# claude-micro-easyeda.net
KiCad netlist of a schematic drawn in EasyEDA
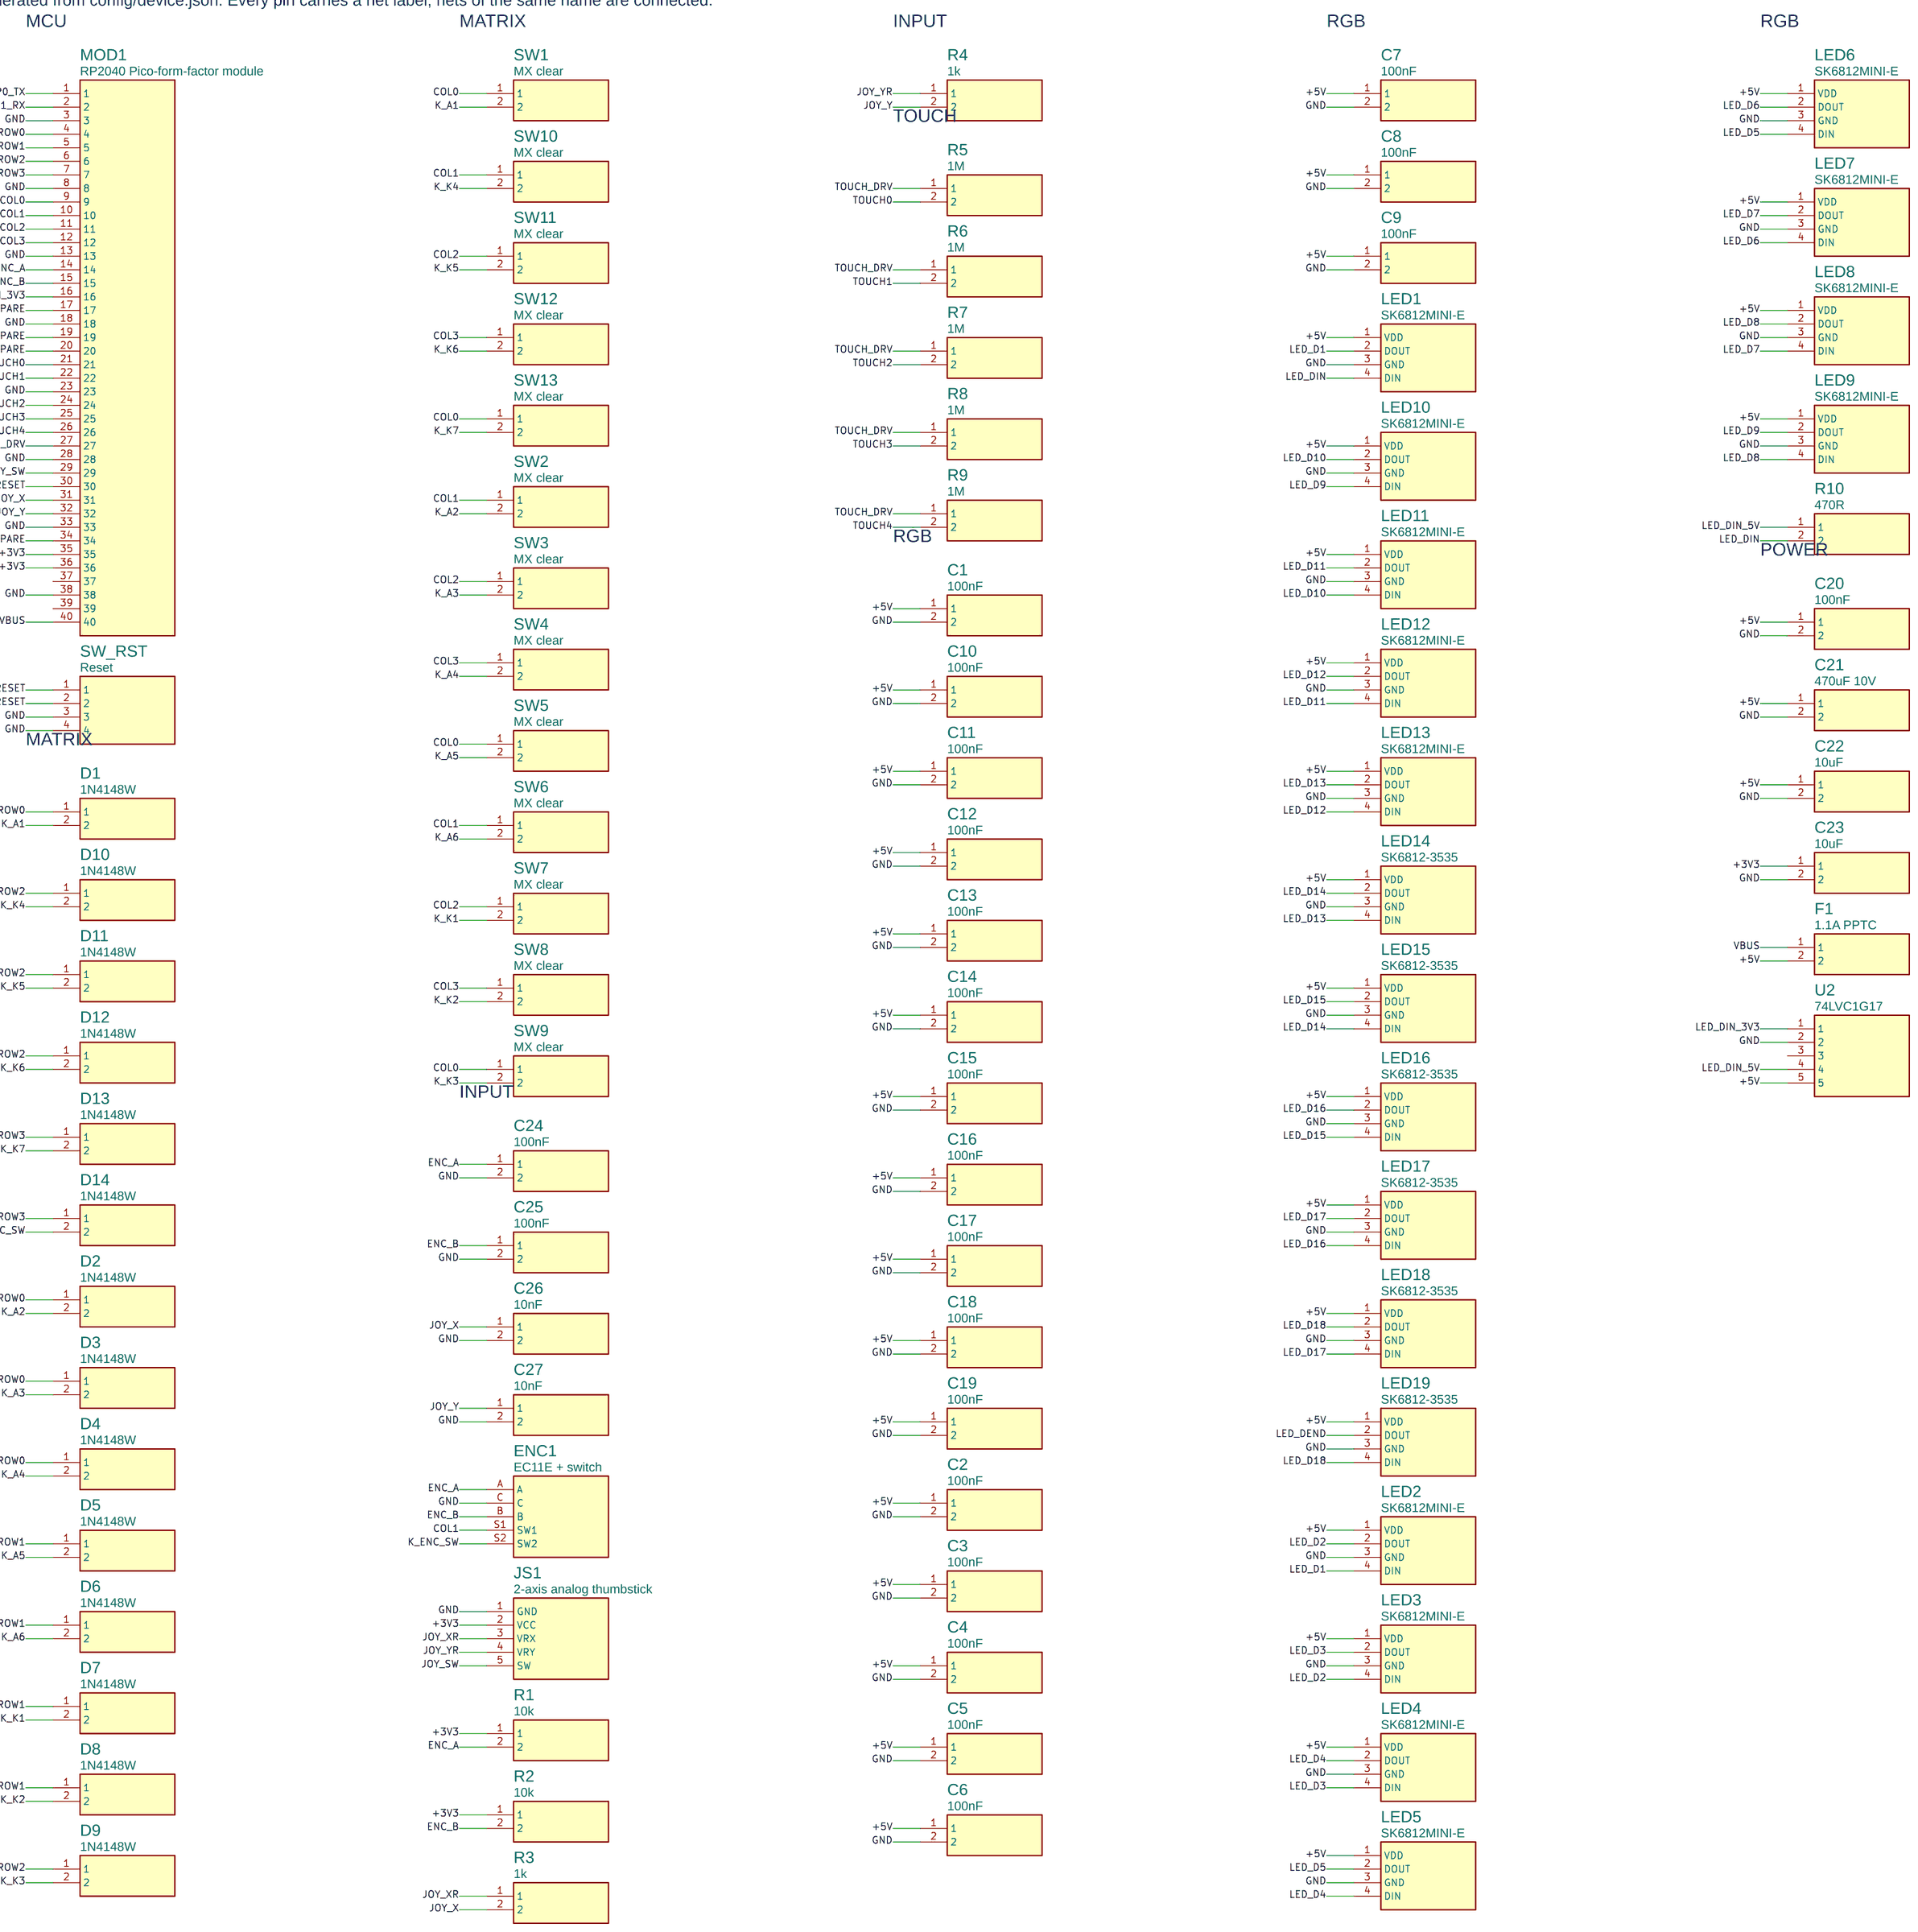
[diagram p0: schematic sheet]

(export (version "E")
  (design (tool "Eeschema 10.0.6"))
  (components
    (comp (ref "C1") (value "100nF") (libsource (lib "") (part "100nF")))
    (comp (ref "C2") (value "100nF") (libsource (lib "") (part "100nF")))
    (comp (ref "C3") (value "100nF") (libsource (lib "") (part "100nF")))
    (comp (ref "C4") (value "100nF") (libsource (lib "") (part "100nF")))
    (comp (ref "C5") (value "100nF") (libsource (lib "") (part "100nF")))
    (comp (ref "C6") (value "100nF") (libsource (lib "") (part "100nF")))
    (comp (ref "C7") (value "100nF") (libsource (lib "") (part "100nF")))
    (comp (ref "C8") (value "100nF") (libsource (lib "") (part "100nF")))
    (comp (ref "C9") (value "100nF") (libsource (lib "") (part "100nF")))
    (comp (ref "C10") (value "100nF") (libsource (lib "") (part "100nF")))
    (comp (ref "C11") (value "100nF") (libsource (lib "") (part "100nF")))
    (comp (ref "C12") (value "100nF") (libsource (lib "") (part "100nF")))
    (comp (ref "C13") (value "100nF") (libsource (lib "") (part "100nF")))
    (comp (ref "C14") (value "100nF") (libsource (lib "") (part "100nF")))
    (comp (ref "C15") (value "100nF") (libsource (lib "") (part "100nF")))
    (comp (ref "C16") (value "100nF") (libsource (lib "") (part "100nF")))
    (comp (ref "C17") (value "100nF") (libsource (lib "") (part "100nF")))
    (comp (ref "C18") (value "100nF") (libsource (lib "") (part "100nF")))
    (comp (ref "C19") (value "100nF") (libsource (lib "") (part "100nF")))
    (comp (ref "C20") (value "100nF") (libsource (lib "") (part "100nF")))
    (comp (ref "C21")
      (value "470uF 10V")
      (fields (field (name "BOM_Manufacturer Part") "Low-ESR bulk"))
      (libsource (lib "") (part "470uF 10V"))
    )
    (comp (ref "C22") (value "10uF") (libsource (lib "") (part "10uF")))
    (comp (ref "C23") (value "10uF") (libsource (lib "") (part "10uF")))
    (comp (ref "C24") (value "100nF") (libsource (lib "") (part "100nF_1")))
    (comp (ref "C25") (value "100nF") (libsource (lib "") (part "100nF_1")))
    (comp (ref "C26") (value "10nF") (libsource (lib "") (part "10nF")))
    (comp (ref "C27") (value "10nF") (libsource (lib "") (part "10nF")))
    (comp (ref "D1")
      (value "1N4148W")
      (fields (field (name "BOM_Manufacturer Part") "1N4148W SOD-123"))
      (libsource (lib "") (part "1N4148W"))
    )
    (comp (ref "D2")
      (value "1N4148W")
      (fields (field (name "BOM_Manufacturer Part") "1N4148W SOD-123"))
      (libsource (lib "") (part "1N4148W"))
    )
    (comp (ref "D3")
      (value "1N4148W")
      (fields (field (name "BOM_Manufacturer Part") "1N4148W SOD-123"))
      (libsource (lib "") (part "1N4148W"))
    )
    (comp (ref "D4")
      (value "1N4148W")
      (fields (field (name "BOM_Manufacturer Part") "1N4148W SOD-123"))
      (libsource (lib "") (part "1N4148W"))
    )
    (comp (ref "D5")
      (value "1N4148W")
      (fields (field (name "BOM_Manufacturer Part") "1N4148W SOD-123"))
      (libsource (lib "") (part "1N4148W"))
    )
    (comp (ref "D6")
      (value "1N4148W")
      (fields (field (name "BOM_Manufacturer Part") "1N4148W SOD-123"))
      (libsource (lib "") (part "1N4148W"))
    )
    (comp (ref "D7")
      (value "1N4148W")
      (fields (field (name "BOM_Manufacturer Part") "1N4148W SOD-123"))
      (libsource (lib "") (part "1N4148W"))
    )
    (comp (ref "D8")
      (value "1N4148W")
      (fields (field (name "BOM_Manufacturer Part") "1N4148W SOD-123"))
      (libsource (lib "") (part "1N4148W"))
    )
    (comp (ref "D9")
      (value "1N4148W")
      (fields (field (name "BOM_Manufacturer Part") "1N4148W SOD-123"))
      (libsource (lib "") (part "1N4148W"))
    )
    (comp (ref "D10")
      (value "1N4148W")
      (fields (field (name "BOM_Manufacturer Part") "1N4148W SOD-123"))
      (libsource (lib "") (part "1N4148W"))
    )
    (comp (ref "D11")
      (value "1N4148W")
      (fields (field (name "BOM_Manufacturer Part") "1N4148W SOD-123"))
      (libsource (lib "") (part "1N4148W"))
    )
    (comp (ref "D12")
      (value "1N4148W")
      (fields (field (name "BOM_Manufacturer Part") "1N4148W SOD-123"))
      (libsource (lib "") (part "1N4148W"))
    )
    (comp (ref "D13")
      (value "1N4148W")
      (fields (field (name "BOM_Manufacturer Part") "1N4148W SOD-123"))
      (libsource (lib "") (part "1N4148W"))
    )
    (comp (ref "D14")
      (value "1N4148W")
      (fields (field (name "BOM_Manufacturer Part") "1N4148W SOD-123"))
      (libsource (lib "") (part "1N4148W"))
    )
    (comp (ref "ENC1")
      (value "EC11E + switch")
      (fields (field (name "BOM_Manufacturer Part") "EC11E15244Ax (9 mm shaft)"))
      (libsource (lib "") (part "EC11E + switch"))
    )
    (comp (ref "F1")
      (value "1.1A PPTC")
      (fields (field (name "BOM_Manufacturer Part") "MF-MSMF110"))
      (libsource (lib "") (part "1.1A PPTC"))
    )
    (comp (ref "JS1")
      (value "2-axis analog thumbstick")
      (fields (field (name "BOM_Manufacturer Part") "20 mm planar thumbstick, 10k pots"))
      (libsource (lib "") (part "2-axis analog thumbstick"))
    )
    (comp (ref "LED1") (value "SK6812MINI-E") (libsource (lib "") (part "SK6812MINI-E")))
    (comp (ref "LED2") (value "SK6812MINI-E") (libsource (lib "") (part "SK6812MINI-E")))
    (comp (ref "LED3") (value "SK6812MINI-E") (libsource (lib "") (part "SK6812MINI-E")))
    (comp (ref "LED4") (value "SK6812MINI-E") (libsource (lib "") (part "SK6812MINI-E")))
    (comp (ref "LED5") (value "SK6812MINI-E") (libsource (lib "") (part "SK6812MINI-E")))
    (comp (ref "LED6") (value "SK6812MINI-E") (libsource (lib "") (part "SK6812MINI-E")))
    (comp (ref "LED7") (value "SK6812MINI-E") (libsource (lib "") (part "SK6812MINI-E")))
    (comp (ref "LED8") (value "SK6812MINI-E") (libsource (lib "") (part "SK6812MINI-E")))
    (comp (ref "LED9") (value "SK6812MINI-E") (libsource (lib "") (part "SK6812MINI-E")))
    (comp (ref "LED10") (value "SK6812MINI-E") (libsource (lib "") (part "SK6812MINI-E")))
    (comp (ref "LED11") (value "SK6812MINI-E") (libsource (lib "") (part "SK6812MINI-E")))
    (comp (ref "LED12") (value "SK6812MINI-E") (libsource (lib "") (part "SK6812MINI-E")))
    (comp (ref "LED13") (value "SK6812MINI-E") (libsource (lib "") (part "SK6812MINI-E")))
    (comp (ref "LED14") (value "SK6812-3535") (libsource (lib "") (part "SK6812-3535")))
    (comp (ref "LED15") (value "SK6812-3535") (libsource (lib "") (part "SK6812-3535")))
    (comp (ref "LED16") (value "SK6812-3535") (libsource (lib "") (part "SK6812-3535")))
    (comp (ref "LED17") (value "SK6812-3535") (libsource (lib "") (part "SK6812-3535")))
    (comp (ref "LED18") (value "SK6812-3535") (libsource (lib "") (part "SK6812-3535")))
    (comp (ref "LED19") (value "SK6812-3535") (libsource (lib "") (part "SK6812-3535")))
    (comp (ref "MOD1")
      (value "RP2040 Pico-form-factor module")
      (fields (field (name "BOM_Manufacturer Part") "YD-RP2040 / RP2040-Plus / Raspberry Pi Pico"))
      (libsource (lib "") (part "RP2040 Pico-form-factor module"))
    )
    (comp (ref "R1") (value "10k") (libsource (lib "") (part "10k")))
    (comp (ref "R2") (value "10k") (libsource (lib "") (part "10k")))
    (comp (ref "R3") (value "1k") (libsource (lib "") (part "1k")))
    (comp (ref "R4") (value "1k") (libsource (lib "") (part "1k")))
    (comp (ref "R5") (value "1M") (libsource (lib "") (part "1M")))
    (comp (ref "R6") (value "1M") (libsource (lib "") (part "1M")))
    (comp (ref "R7") (value "1M") (libsource (lib "") (part "1M")))
    (comp (ref "R8") (value "1M") (libsource (lib "") (part "1M")))
    (comp (ref "R9") (value "1M") (libsource (lib "") (part "1M")))
    (comp (ref "R10") (value "470R") (libsource (lib "") (part "470R")))
    (comp (ref "SW1")
      (value "MX clear")
      (fields (field (name "BOM_Manufacturer Part") "MX-compatible, clear housing, 5-pin"))
      (libsource (lib "") (part "MX clear"))
    )
    (comp (ref "SW2")
      (value "MX clear")
      (fields (field (name "BOM_Manufacturer Part") "MX-compatible, clear housing, 5-pin"))
      (libsource (lib "") (part "MX clear"))
    )
    (comp (ref "SW3")
      (value "MX clear")
      (fields (field (name "BOM_Manufacturer Part") "MX-compatible, clear housing, 5-pin"))
      (libsource (lib "") (part "MX clear"))
    )
    (comp (ref "SW4")
      (value "MX clear")
      (fields (field (name "BOM_Manufacturer Part") "MX-compatible, clear housing, 5-pin"))
      (libsource (lib "") (part "MX clear"))
    )
    (comp (ref "SW5")
      (value "MX clear")
      (fields (field (name "BOM_Manufacturer Part") "MX-compatible, clear housing, 5-pin"))
      (libsource (lib "") (part "MX clear"))
    )
    (comp (ref "SW6")
      (value "MX clear")
      (fields (field (name "BOM_Manufacturer Part") "MX-compatible, clear housing, 5-pin"))
      (libsource (lib "") (part "MX clear"))
    )
    (comp (ref "SW7")
      (value "MX clear")
      (fields (field (name "BOM_Manufacturer Part") "MX-compatible, clear housing, 5-pin"))
      (libsource (lib "") (part "MX clear"))
    )
    (comp (ref "SW8")
      (value "MX clear")
      (fields (field (name "BOM_Manufacturer Part") "MX-compatible, clear housing, 5-pin"))
      (libsource (lib "") (part "MX clear"))
    )
    (comp (ref "SW9")
      (value "MX clear")
      (fields (field (name "BOM_Manufacturer Part") "MX-compatible, clear housing, 5-pin"))
      (libsource (lib "") (part "MX clear"))
    )
    (comp (ref "SW10")
      (value "MX clear")
      (fields (field (name "BOM_Manufacturer Part") "MX-compatible, clear housing, 5-pin"))
      (libsource (lib "") (part "MX clear"))
    )
    (comp (ref "SW11")
      (value "MX clear")
      (fields (field (name "BOM_Manufacturer Part") "MX-compatible, clear housing, 5-pin"))
      (libsource (lib "") (part "MX clear"))
    )
    (comp (ref "SW12")
      (value "MX clear")
      (fields (field (name "BOM_Manufacturer Part") "MX-compatible, clear housing, 5-pin"))
      (libsource (lib "") (part "MX clear"))
    )
    (comp (ref "SW13")
      (value "MX clear")
      (fields (field (name "BOM_Manufacturer Part") "MX-compatible, clear housing, 5-pin"))
      (libsource (lib "") (part "MX clear"))
    )
    (comp (ref "SW_RST") (value "Reset") (libsource (lib "") (part "Reset")))
    (comp (ref "U2")
      (value "74LVC1G17")
      (fields (field (name "BOM_Manufacturer Part") "SN74LVC1G17DBVR"))
      (libsource (lib "") (part "74LVC1G17"))
    )
  )
  (nets
    (net (code "1") (name "/+3V3") (class "Default")
      (node (ref "C23") (pin "1") (pinfunction "1_1") (pintype "passive"))
      (node (ref "JS1") (pin "2") (pinfunction "VCC_2") (pintype "passive"))
      (node (ref "MOD1") (pin "35") (pinfunction "35_35") (pintype "passive"))
      (node (ref "MOD1") (pin "36") (pinfunction "36_36") (pintype "passive"))
      (node (ref "R1") (pin "1") (pinfunction "1_1") (pintype "passive"))
      (node (ref "R2") (pin "1") (pinfunction "1_1") (pintype "passive"))
    )
    (net (code "2") (name "/+5V") (class "Default")
      (node (ref "C1") (pin "1") (pinfunction "1_1") (pintype "passive"))
      (node (ref "C10") (pin "1") (pinfunction "1_1") (pintype "passive"))
      (node (ref "C11") (pin "1") (pinfunction "1_1") (pintype "passive"))
      (node (ref "C12") (pin "1") (pinfunction "1_1") (pintype "passive"))
      (node (ref "C13") (pin "1") (pinfunction "1_1") (pintype "passive"))
      (node (ref "C14") (pin "1") (pinfunction "1_1") (pintype "passive"))
      (node (ref "C15") (pin "1") (pinfunction "1_1") (pintype "passive"))
      (node (ref "C16") (pin "1") (pinfunction "1_1") (pintype "passive"))
      (node (ref "C17") (pin "1") (pinfunction "1_1") (pintype "passive"))
      (node (ref "C18") (pin "1") (pinfunction "1_1") (pintype "passive"))
      (node (ref "C19") (pin "1") (pinfunction "1_1") (pintype "passive"))
      (node (ref "C2") (pin "1") (pinfunction "1_1") (pintype "passive"))
      (node (ref "C20") (pin "1") (pinfunction "1_1") (pintype "passive"))
      (node (ref "C21") (pin "1") (pinfunction "1_1") (pintype "passive"))
      (node (ref "C22") (pin "1") (pinfunction "1_1") (pintype "passive"))
      (node (ref "C3") (pin "1") (pinfunction "1_1") (pintype "passive"))
      (node (ref "C4") (pin "1") (pinfunction "1_1") (pintype "passive"))
      (node (ref "C5") (pin "1") (pinfunction "1_1") (pintype "passive"))
      (node (ref "C6") (pin "1") (pinfunction "1_1") (pintype "passive"))
      (node (ref "C7") (pin "1") (pinfunction "1_1") (pintype "passive"))
      (node (ref "C8") (pin "1") (pinfunction "1_1") (pintype "passive"))
      (node (ref "C9") (pin "1") (pinfunction "1_1") (pintype "passive"))
      (node (ref "F1") (pin "2") (pinfunction "2_2") (pintype "passive"))
      (node (ref "LED1") (pin "1") (pinfunction "VDD_1") (pintype "passive"))
      (node (ref "LED10") (pin "1") (pinfunction "VDD_1") (pintype "passive"))
      (node (ref "LED11") (pin "1") (pinfunction "VDD_1") (pintype "passive"))
      (node (ref "LED12") (pin "1") (pinfunction "VDD_1") (pintype "passive"))
      (node (ref "LED13") (pin "1") (pinfunction "VDD_1") (pintype "passive"))
      (node (ref "LED14") (pin "1") (pinfunction "VDD_1") (pintype "passive"))
      (node (ref "LED15") (pin "1") (pinfunction "VDD_1") (pintype "passive"))
      (node (ref "LED16") (pin "1") (pinfunction "VDD_1") (pintype "passive"))
      (node (ref "LED17") (pin "1") (pinfunction "VDD_1") (pintype "passive"))
      (node (ref "LED18") (pin "1") (pinfunction "VDD_1") (pintype "passive"))
      (node (ref "LED19") (pin "1") (pinfunction "VDD_1") (pintype "passive"))
      (node (ref "LED2") (pin "1") (pinfunction "VDD_1") (pintype "passive"))
      (node (ref "LED3") (pin "1") (pinfunction "VDD_1") (pintype "passive"))
      (node (ref "LED4") (pin "1") (pinfunction "VDD_1") (pintype "passive"))
      (node (ref "LED5") (pin "1") (pinfunction "VDD_1") (pintype "passive"))
      (node (ref "LED6") (pin "1") (pinfunction "VDD_1") (pintype "passive"))
      (node (ref "LED7") (pin "1") (pinfunction "VDD_1") (pintype "passive"))
      (node (ref "LED8") (pin "1") (pinfunction "VDD_1") (pintype "passive"))
      (node (ref "LED9") (pin "1") (pinfunction "VDD_1") (pintype "passive"))
      (node (ref "U2") (pin "5") (pinfunction "5_5") (pintype "passive"))
    )
    (net (code "3") (name "/COL0") (class "Default")
      (node (ref "MOD1") (pin "9") (pinfunction "9_9") (pintype "bidirectional"))
      (node (ref "SW1") (pin "1") (pinfunction "1_1") (pintype "bidirectional"))
      (node (ref "SW13") (pin "1") (pinfunction "1_1") (pintype "bidirectional"))
      (node (ref "SW5") (pin "1") (pinfunction "1_1") (pintype "bidirectional"))
      (node (ref "SW9") (pin "1") (pinfunction "1_1") (pintype "bidirectional"))
    )
    (net (code "4") (name "/COL1") (class "Default")
      (node (ref "ENC1") (pin "S1") (pinfunction "SW1_S1") (pintype "bidirectional"))
      (node (ref "MOD1") (pin "10") (pinfunction "10_10") (pintype "bidirectional"))
      (node (ref "SW10") (pin "1") (pinfunction "1_1") (pintype "bidirectional"))
      (node (ref "SW2") (pin "1") (pinfunction "1_1") (pintype "bidirectional"))
      (node (ref "SW6") (pin "1") (pinfunction "1_1") (pintype "bidirectional"))
    )
    (net (code "5") (name "/COL2") (class "Default")
      (node (ref "MOD1") (pin "11") (pinfunction "11_11") (pintype "bidirectional"))
      (node (ref "SW11") (pin "1") (pinfunction "1_1") (pintype "bidirectional"))
      (node (ref "SW3") (pin "1") (pinfunction "1_1") (pintype "bidirectional"))
      (node (ref "SW7") (pin "1") (pinfunction "1_1") (pintype "bidirectional"))
    )
    (net (code "6") (name "/COL3") (class "Default")
      (node (ref "MOD1") (pin "12") (pinfunction "12_12") (pintype "bidirectional"))
      (node (ref "SW12") (pin "1") (pinfunction "1_1") (pintype "bidirectional"))
      (node (ref "SW4") (pin "1") (pinfunction "1_1") (pintype "bidirectional"))
      (node (ref "SW8") (pin "1") (pinfunction "1_1") (pintype "bidirectional"))
    )
    (net (code "7") (name "/ENC_A") (class "Default")
      (node (ref "C24") (pin "1") (pinfunction "1_1") (pintype "bidirectional"))
      (node (ref "ENC1") (pin "A") (pinfunction "A_A") (pintype "bidirectional"))
      (node (ref "MOD1") (pin "14") (pinfunction "14_14") (pintype "bidirectional"))
      (node (ref "R1") (pin "2") (pinfunction "2_2") (pintype "bidirectional"))
    )
    (net (code "8") (name "/ENC_B") (class "Default")
      (node (ref "C25") (pin "1") (pinfunction "1_1") (pintype "bidirectional"))
      (node (ref "ENC1") (pin "B") (pinfunction "B_B") (pintype "bidirectional"))
      (node (ref "MOD1") (pin "15") (pinfunction "15_15") (pintype "bidirectional"))
      (node (ref "R2") (pin "2") (pinfunction "2_2") (pintype "bidirectional"))
    )
    (net (code "9") (name "/GND") (class "Default")
      (node (ref "C1") (pin "2") (pinfunction "2_2") (pintype "passive"))
      (node (ref "C10") (pin "2") (pinfunction "2_2") (pintype "passive"))
      (node (ref "C11") (pin "2") (pinfunction "2_2") (pintype "passive"))
      (node (ref "C12") (pin "2") (pinfunction "2_2") (pintype "passive"))
      (node (ref "C13") (pin "2") (pinfunction "2_2") (pintype "passive"))
      (node (ref "C14") (pin "2") (pinfunction "2_2") (pintype "passive"))
      (node (ref "C15") (pin "2") (pinfunction "2_2") (pintype "passive"))
      (node (ref "C16") (pin "2") (pinfunction "2_2") (pintype "passive"))
      (node (ref "C17") (pin "2") (pinfunction "2_2") (pintype "passive"))
      (node (ref "C18") (pin "2") (pinfunction "2_2") (pintype "passive"))
      (node (ref "C19") (pin "2") (pinfunction "2_2") (pintype "passive"))
      (node (ref "C2") (pin "2") (pinfunction "2_2") (pintype "passive"))
      (node (ref "C20") (pin "2") (pinfunction "2_2") (pintype "passive"))
      (node (ref "C21") (pin "2") (pinfunction "2_2") (pintype "passive"))
      (node (ref "C22") (pin "2") (pinfunction "2_2") (pintype "passive"))
      (node (ref "C23") (pin "2") (pinfunction "2_2") (pintype "passive"))
      (node (ref "C24") (pin "2") (pinfunction "2_2") (pintype "passive"))
      (node (ref "C25") (pin "2") (pinfunction "2_2") (pintype "passive"))
      (node (ref "C26") (pin "2") (pinfunction "2_2") (pintype "passive"))
      (node (ref "C27") (pin "2") (pinfunction "2_2") (pintype "passive"))
      (node (ref "C3") (pin "2") (pinfunction "2_2") (pintype "passive"))
      (node (ref "C4") (pin "2") (pinfunction "2_2") (pintype "passive"))
      (node (ref "C5") (pin "2") (pinfunction "2_2") (pintype "passive"))
      (node (ref "C6") (pin "2") (pinfunction "2_2") (pintype "passive"))
      (node (ref "C7") (pin "2") (pinfunction "2_2") (pintype "passive"))
      (node (ref "C8") (pin "2") (pinfunction "2_2") (pintype "passive"))
      (node (ref "C9") (pin "2") (pinfunction "2_2") (pintype "passive"))
      (node (ref "ENC1") (pin "C") (pinfunction "C_C") (pintype "passive"))
      (node (ref "JS1") (pin "1") (pinfunction "GND_1") (pintype "passive"))
      (node (ref "LED1") (pin "3") (pinfunction "GND_3") (pintype "passive"))
      (node (ref "LED10") (pin "3") (pinfunction "GND_3") (pintype "passive"))
      (node (ref "LED11") (pin "3") (pinfunction "GND_3") (pintype "passive"))
      (node (ref "LED12") (pin "3") (pinfunction "GND_3") (pintype "passive"))
      (node (ref "LED13") (pin "3") (pinfunction "GND_3") (pintype "passive"))
      (node (ref "LED14") (pin "3") (pinfunction "GND_3") (pintype "passive"))
      (node (ref "LED15") (pin "3") (pinfunction "GND_3") (pintype "passive"))
      (node (ref "LED16") (pin "3") (pinfunction "GND_3") (pintype "passive"))
      (node (ref "LED17") (pin "3") (pinfunction "GND_3") (pintype "passive"))
      (node (ref "LED18") (pin "3") (pinfunction "GND_3") (pintype "passive"))
      (node (ref "LED19") (pin "3") (pinfunction "GND_3") (pintype "passive"))
      (node (ref "LED2") (pin "3") (pinfunction "GND_3") (pintype "passive"))
      (node (ref "LED3") (pin "3") (pinfunction "GND_3") (pintype "passive"))
      (node (ref "LED4") (pin "3") (pinfunction "GND_3") (pintype "passive"))
      (node (ref "LED5") (pin "3") (pinfunction "GND_3") (pintype "passive"))
      (node (ref "LED6") (pin "3") (pinfunction "GND_3") (pintype "passive"))
      (node (ref "LED7") (pin "3") (pinfunction "GND_3") (pintype "passive"))
      (node (ref "LED8") (pin "3") (pinfunction "GND_3") (pintype "passive"))
      (node (ref "LED9") (pin "3") (pinfunction "GND_3") (pintype "passive"))
      (node (ref "MOD1") (pin "13") (pinfunction "13_13") (pintype "passive"))
      (node (ref "MOD1") (pin "18") (pinfunction "18_18") (pintype "passive"))
      (node (ref "MOD1") (pin "23") (pinfunction "23_23") (pintype "passive"))
      (node (ref "MOD1") (pin "28") (pinfunction "28_28") (pintype "passive"))
      (node (ref "MOD1") (pin "3") (pinfunction "3_3") (pintype "passive"))
      (node (ref "MOD1") (pin "33") (pinfunction "33_33") (pintype "passive"))
      (node (ref "MOD1") (pin "38") (pinfunction "38_38") (pintype "passive"))
      (node (ref "MOD1") (pin "8") (pinfunction "8_8") (pintype "passive"))
      (node (ref "SW_RST") (pin "3") (pinfunction "3_3") (pintype "passive"))
      (node (ref "SW_RST") (pin "4") (pinfunction "4_4") (pintype "passive"))
      (node (ref "U2") (pin "2") (pinfunction "2_2") (pintype "passive"))
    )
    (net (code "10") (name "/GP0_TX") (class "Default")
      (node (ref "MOD1") (pin "1") (pinfunction "1_1") (pintype "bidirectional"))
    )
    (net (code "11") (name "/GP1_RX") (class "Default")
      (node (ref "MOD1") (pin "2") (pinfunction "2_2") (pintype "bidirectional"))
    )
    (net (code "12") (name "/GP13_SPARE") (class "Default")
      (node (ref "MOD1") (pin "17") (pinfunction "17_17") (pintype "bidirectional"))
    )
    (net (code "13") (name "/GP14_SPARE") (class "Default")
      (node (ref "MOD1") (pin "19") (pinfunction "19_19") (pintype "bidirectional"))
    )
    (net (code "14") (name "/GP15_SPARE") (class "Default")
      (node (ref "MOD1") (pin "20") (pinfunction "20_20") (pintype "bidirectional"))
    )
    (net (code "15") (name "/GP28_SPARE") (class "Default")
      (node (ref "MOD1") (pin "34") (pinfunction "34_34") (pintype "bidirectional"))
    )
    (net (code "16") (name "/JOY_SW") (class "Default")
      (node (ref "JS1") (pin "5") (pinfunction "SW_5") (pintype "bidirectional"))
      (node (ref "MOD1") (pin "29") (pinfunction "29_29") (pintype "bidirectional"))
    )
    (net (code "17") (name "/JOY_X") (class "Default")
      (node (ref "C26") (pin "1") (pinfunction "1_1") (pintype "bidirectional"))
      (node (ref "MOD1") (pin "31") (pinfunction "31_31") (pintype "bidirectional"))
      (node (ref "R3") (pin "2") (pinfunction "2_2") (pintype "bidirectional"))
    )
    (net (code "18") (name "/JOY_XR") (class "Default")
      (node (ref "JS1") (pin "3") (pinfunction "VRX_3") (pintype "bidirectional"))
      (node (ref "R3") (pin "1") (pinfunction "1_1") (pintype "bidirectional"))
    )
    (net (code "19") (name "/JOY_Y") (class "Default")
      (node (ref "C27") (pin "1") (pinfunction "1_1") (pintype "bidirectional"))
      (node (ref "MOD1") (pin "32") (pinfunction "32_32") (pintype "bidirectional"))
      (node (ref "R4") (pin "2") (pinfunction "2_2") (pintype "bidirectional"))
    )
    (net (code "20") (name "/JOY_YR") (class "Default")
      (node (ref "JS1") (pin "4") (pinfunction "VRY_4") (pintype "bidirectional"))
      (node (ref "R4") (pin "1") (pinfunction "1_1") (pintype "bidirectional"))
    )
    (net (code "21") (name "/K_A1") (class "Default")
      (node (ref "D1") (pin "2") (pinfunction "2_2") (pintype "bidirectional"))
      (node (ref "SW1") (pin "2") (pinfunction "2_2") (pintype "bidirectional"))
    )
    (net (code "22") (name "/K_A2") (class "Default")
      (node (ref "D2") (pin "2") (pinfunction "2_2") (pintype "bidirectional"))
      (node (ref "SW2") (pin "2") (pinfunction "2_2") (pintype "bidirectional"))
    )
    (net (code "23") (name "/K_A3") (class "Default")
      (node (ref "D3") (pin "2") (pinfunction "2_2") (pintype "bidirectional"))
      (node (ref "SW3") (pin "2") (pinfunction "2_2") (pintype "bidirectional"))
    )
    (net (code "24") (name "/K_A4") (class "Default")
      (node (ref "D4") (pin "2") (pinfunction "2_2") (pintype "bidirectional"))
      (node (ref "SW4") (pin "2") (pinfunction "2_2") (pintype "bidirectional"))
    )
    (net (code "25") (name "/K_A5") (class "Default")
      (node (ref "D5") (pin "2") (pinfunction "2_2") (pintype "bidirectional"))
      (node (ref "SW5") (pin "2") (pinfunction "2_2") (pintype "bidirectional"))
    )
    (net (code "26") (name "/K_A6") (class "Default")
      (node (ref "D6") (pin "2") (pinfunction "2_2") (pintype "bidirectional"))
      (node (ref "SW6") (pin "2") (pinfunction "2_2") (pintype "bidirectional"))
    )
    (net (code "27") (name "/K_ENC_SW") (class "Default")
      (node (ref "D14") (pin "2") (pinfunction "2_2") (pintype "bidirectional"))
      (node (ref "ENC1") (pin "S2") (pinfunction "SW2_S2") (pintype "bidirectional"))
    )
    (net (code "28") (name "/K_K1") (class "Default")
      (node (ref "D7") (pin "2") (pinfunction "2_2") (pintype "bidirectional"))
      (node (ref "SW7") (pin "2") (pinfunction "2_2") (pintype "bidirectional"))
    )
    (net (code "29") (name "/K_K2") (class "Default")
      (node (ref "D8") (pin "2") (pinfunction "2_2") (pintype "bidirectional"))
      (node (ref "SW8") (pin "2") (pinfunction "2_2") (pintype "bidirectional"))
    )
    (net (code "30") (name "/K_K3") (class "Default")
      (node (ref "D9") (pin "2") (pinfunction "2_2") (pintype "bidirectional"))
      (node (ref "SW9") (pin "2") (pinfunction "2_2") (pintype "bidirectional"))
    )
    (net (code "31") (name "/K_K4") (class "Default")
      (node (ref "D10") (pin "2") (pinfunction "2_2") (pintype "bidirectional"))
      (node (ref "SW10") (pin "2") (pinfunction "2_2") (pintype "bidirectional"))
    )
    (net (code "32") (name "/K_K5") (class "Default")
      (node (ref "D11") (pin "2") (pinfunction "2_2") (pintype "bidirectional"))
      (node (ref "SW11") (pin "2") (pinfunction "2_2") (pintype "bidirectional"))
    )
    (net (code "33") (name "/K_K6") (class "Default")
      (node (ref "D12") (pin "2") (pinfunction "2_2") (pintype "bidirectional"))
      (node (ref "SW12") (pin "2") (pinfunction "2_2") (pintype "bidirectional"))
    )
    (net (code "34") (name "/K_K7") (class "Default")
      (node (ref "D13") (pin "2") (pinfunction "2_2") (pintype "bidirectional"))
      (node (ref "SW13") (pin "2") (pinfunction "2_2") (pintype "bidirectional"))
    )
    (net (code "35") (name "/LED_D1") (class "Default")
      (node (ref "LED1") (pin "2") (pinfunction "DOUT_2") (pintype "bidirectional"))
      (node (ref "LED2") (pin "4") (pinfunction "DIN_4") (pintype "bidirectional"))
    )
    (net (code "36") (name "/LED_D2") (class "Default")
      (node (ref "LED2") (pin "2") (pinfunction "DOUT_2") (pintype "bidirectional"))
      (node (ref "LED3") (pin "4") (pinfunction "DIN_4") (pintype "bidirectional"))
    )
    (net (code "37") (name "/LED_D3") (class "Default")
      (node (ref "LED3") (pin "2") (pinfunction "DOUT_2") (pintype "bidirectional"))
      (node (ref "LED4") (pin "4") (pinfunction "DIN_4") (pintype "bidirectional"))
    )
    (net (code "38") (name "/LED_D4") (class "Default")
      (node (ref "LED4") (pin "2") (pinfunction "DOUT_2") (pintype "bidirectional"))
      (node (ref "LED5") (pin "4") (pinfunction "DIN_4") (pintype "bidirectional"))
    )
    (net (code "39") (name "/LED_D5") (class "Default")
      (node (ref "LED5") (pin "2") (pinfunction "DOUT_2") (pintype "bidirectional"))
      (node (ref "LED6") (pin "4") (pinfunction "DIN_4") (pintype "bidirectional"))
    )
    (net (code "40") (name "/LED_D6") (class "Default")
      (node (ref "LED6") (pin "2") (pinfunction "DOUT_2") (pintype "bidirectional"))
      (node (ref "LED7") (pin "4") (pinfunction "DIN_4") (pintype "bidirectional"))
    )
    (net (code "41") (name "/LED_D7") (class "Default")
      (node (ref "LED7") (pin "2") (pinfunction "DOUT_2") (pintype "bidirectional"))
      (node (ref "LED8") (pin "4") (pinfunction "DIN_4") (pintype "bidirectional"))
    )
    (net (code "42") (name "/LED_D8") (class "Default")
      (node (ref "LED8") (pin "2") (pinfunction "DOUT_2") (pintype "bidirectional"))
      (node (ref "LED9") (pin "4") (pinfunction "DIN_4") (pintype "bidirectional"))
    )
    (net (code "43") (name "/LED_D9") (class "Default")
      (node (ref "LED10") (pin "4") (pinfunction "DIN_4") (pintype "bidirectional"))
      (node (ref "LED9") (pin "2") (pinfunction "DOUT_2") (pintype "bidirectional"))
    )
    (net (code "44") (name "/LED_D10") (class "Default")
      (node (ref "LED10") (pin "2") (pinfunction "DOUT_2") (pintype "bidirectional"))
      (node (ref "LED11") (pin "4") (pinfunction "DIN_4") (pintype "bidirectional"))
    )
    (net (code "45") (name "/LED_D11") (class "Default")
      (node (ref "LED11") (pin "2") (pinfunction "DOUT_2") (pintype "bidirectional"))
      (node (ref "LED12") (pin "4") (pinfunction "DIN_4") (pintype "bidirectional"))
    )
    (net (code "46") (name "/LED_D12") (class "Default")
      (node (ref "LED12") (pin "2") (pinfunction "DOUT_2") (pintype "bidirectional"))
      (node (ref "LED13") (pin "4") (pinfunction "DIN_4") (pintype "bidirectional"))
    )
    (net (code "47") (name "/LED_D13") (class "Default")
      (node (ref "LED13") (pin "2") (pinfunction "DOUT_2") (pintype "bidirectional"))
      (node (ref "LED14") (pin "4") (pinfunction "DIN_4") (pintype "bidirectional"))
    )
    (net (code "48") (name "/LED_D14") (class "Default")
      (node (ref "LED14") (pin "2") (pinfunction "DOUT_2") (pintype "bidirectional"))
      (node (ref "LED15") (pin "4") (pinfunction "DIN_4") (pintype "bidirectional"))
    )
    (net (code "49") (name "/LED_D15") (class "Default")
      (node (ref "LED15") (pin "2") (pinfunction "DOUT_2") (pintype "bidirectional"))
      (node (ref "LED16") (pin "4") (pinfunction "DIN_4") (pintype "bidirectional"))
    )
    (net (code "50") (name "/LED_D16") (class "Default")
      (node (ref "LED16") (pin "2") (pinfunction "DOUT_2") (pintype "bidirectional"))
      (node (ref "LED17") (pin "4") (pinfunction "DIN_4") (pintype "bidirectional"))
    )
    (net (code "51") (name "/LED_D17") (class "Default")
      (node (ref "LED17") (pin "2") (pinfunction "DOUT_2") (pintype "bidirectional"))
      (node (ref "LED18") (pin "4") (pinfunction "DIN_4") (pintype "bidirectional"))
    )
    (net (code "52") (name "/LED_D18") (class "Default")
      (node (ref "LED18") (pin "2") (pinfunction "DOUT_2") (pintype "bidirectional"))
      (node (ref "LED19") (pin "4") (pinfunction "DIN_4") (pintype "bidirectional"))
    )
    (net (code "53") (name "/LED_DEND") (class "Default")
      (node (ref "LED19") (pin "2") (pinfunction "DOUT_2") (pintype "bidirectional"))
    )
    (net (code "54") (name "/LED_DIN") (class "Default")
      (node (ref "LED1") (pin "4") (pinfunction "DIN_4") (pintype "bidirectional"))
      (node (ref "R10") (pin "2") (pinfunction "2_2") (pintype "bidirectional"))
    )
    (net (code "55") (name "/LED_DIN_3V3") (class "Default")
      (node (ref "MOD1") (pin "16") (pinfunction "16_16") (pintype "bidirectional"))
      (node (ref "U2") (pin "1") (pinfunction "1_1") (pintype "bidirectional"))
    )
    (net (code "56") (name "/LED_DIN_5V") (class "Default")
      (node (ref "R10") (pin "1") (pinfunction "1_1") (pintype "bidirectional"))
      (node (ref "U2") (pin "4") (pinfunction "4_4") (pintype "bidirectional"))
    )
    (net (code "57") (name "/RESET") (class "Default")
      (node (ref "MOD1") (pin "30") (pinfunction "30_30") (pintype "bidirectional"))
      (node (ref "SW_RST") (pin "1") (pinfunction "1_1") (pintype "bidirectional"))
      (node (ref "SW_RST") (pin "2") (pinfunction "2_2") (pintype "bidirectional"))
    )
    (net (code "58") (name "/ROW0") (class "Default")
      (node (ref "D1") (pin "1") (pinfunction "1_1") (pintype "bidirectional"))
      (node (ref "D2") (pin "1") (pinfunction "1_1") (pintype "bidirectional"))
      (node (ref "D3") (pin "1") (pinfunction "1_1") (pintype "bidirectional"))
      (node (ref "D4") (pin "1") (pinfunction "1_1") (pintype "bidirectional"))
      (node (ref "MOD1") (pin "4") (pinfunction "4_4") (pintype "bidirectional"))
    )
    (net (code "59") (name "/ROW1") (class "Default")
      (node (ref "D5") (pin "1") (pinfunction "1_1") (pintype "bidirectional"))
      (node (ref "D6") (pin "1") (pinfunction "1_1") (pintype "bidirectional"))
      (node (ref "D7") (pin "1") (pinfunction "1_1") (pintype "bidirectional"))
      (node (ref "D8") (pin "1") (pinfunction "1_1") (pintype "bidirectional"))
      (node (ref "MOD1") (pin "5") (pinfunction "5_5") (pintype "bidirectional"))
    )
    (net (code "60") (name "/ROW2") (class "Default")
      (node (ref "D10") (pin "1") (pinfunction "1_1") (pintype "bidirectional"))
      (node (ref "D11") (pin "1") (pinfunction "1_1") (pintype "bidirectional"))
      (node (ref "D12") (pin "1") (pinfunction "1_1") (pintype "bidirectional"))
      (node (ref "D9") (pin "1") (pinfunction "1_1") (pintype "bidirectional"))
      (node (ref "MOD1") (pin "6") (pinfunction "6_6") (pintype "bidirectional"))
    )
    (net (code "61") (name "/ROW3") (class "Default")
      (node (ref "D13") (pin "1") (pinfunction "1_1") (pintype "bidirectional"))
      (node (ref "D14") (pin "1") (pinfunction "1_1") (pintype "bidirectional"))
      (node (ref "MOD1") (pin "7") (pinfunction "7_7") (pintype "bidirectional"))
    )
    (net (code "62") (name "/TOUCH0") (class "Default")
      (node (ref "MOD1") (pin "21") (pinfunction "21_21") (pintype "bidirectional"))
      (node (ref "R5") (pin "2") (pinfunction "2_2") (pintype "bidirectional"))
    )
    (net (code "63") (name "/TOUCH1") (class "Default")
      (node (ref "MOD1") (pin "22") (pinfunction "22_22") (pintype "bidirectional"))
      (node (ref "R6") (pin "2") (pinfunction "2_2") (pintype "bidirectional"))
    )
    (net (code "64") (name "/TOUCH2") (class "Default")
      (node (ref "MOD1") (pin "24") (pinfunction "24_24") (pintype "bidirectional"))
      (node (ref "R7") (pin "2") (pinfunction "2_2") (pintype "bidirectional"))
    )
    (net (code "65") (name "/TOUCH3") (class "Default")
      (node (ref "MOD1") (pin "25") (pinfunction "25_25") (pintype "bidirectional"))
      (node (ref "R8") (pin "2") (pinfunction "2_2") (pintype "bidirectional"))
    )
    (net (code "66") (name "/TOUCH4") (class "Default")
      (node (ref "MOD1") (pin "26") (pinfunction "26_26") (pintype "bidirectional"))
      (node (ref "R9") (pin "2") (pinfunction "2_2") (pintype "bidirectional"))
    )
    (net (code "67") (name "/TOUCH_DRV") (class "Default")
      (node (ref "MOD1") (pin "27") (pinfunction "27_27") (pintype "bidirectional"))
      (node (ref "R5") (pin "1") (pinfunction "1_1") (pintype "bidirectional"))
      (node (ref "R6") (pin "1") (pinfunction "1_1") (pintype "bidirectional"))
      (node (ref "R7") (pin "1") (pinfunction "1_1") (pintype "bidirectional"))
      (node (ref "R8") (pin "1") (pinfunction "1_1") (pintype "bidirectional"))
      (node (ref "R9") (pin "1") (pinfunction "1_1") (pintype "bidirectional"))
    )
    (net (code "68") (name "/VBUS") (class "Default")
      (node (ref "F1") (pin "1") (pinfunction "1_1") (pintype "passive"))
      (node (ref "MOD1") (pin "40") (pinfunction "40_40") (pintype "passive"))
    )
    (net (code "69") (name "unconnected-(MOD1-Pad37)") (class "Default")
      (node (ref "MOD1") (pin "37") (pinfunction "37_37") (pintype "bidirectional"))
    )
    (net (code "70") (name "unconnected-(MOD1-Pad39)") (class "Default")
      (node (ref "MOD1") (pin "39") (pinfunction "39_39") (pintype "bidirectional"))
    )
    (net (code "71") (name "unconnected-(U2-Pad3)") (class "Default")
      (node (ref "U2") (pin "3") (pinfunction "3_3") (pintype "bidirectional"))
    )
  )
)
